# SCH_WINGLET_IO.net
KiCad netlist of a schematic drawn in Altium Designer
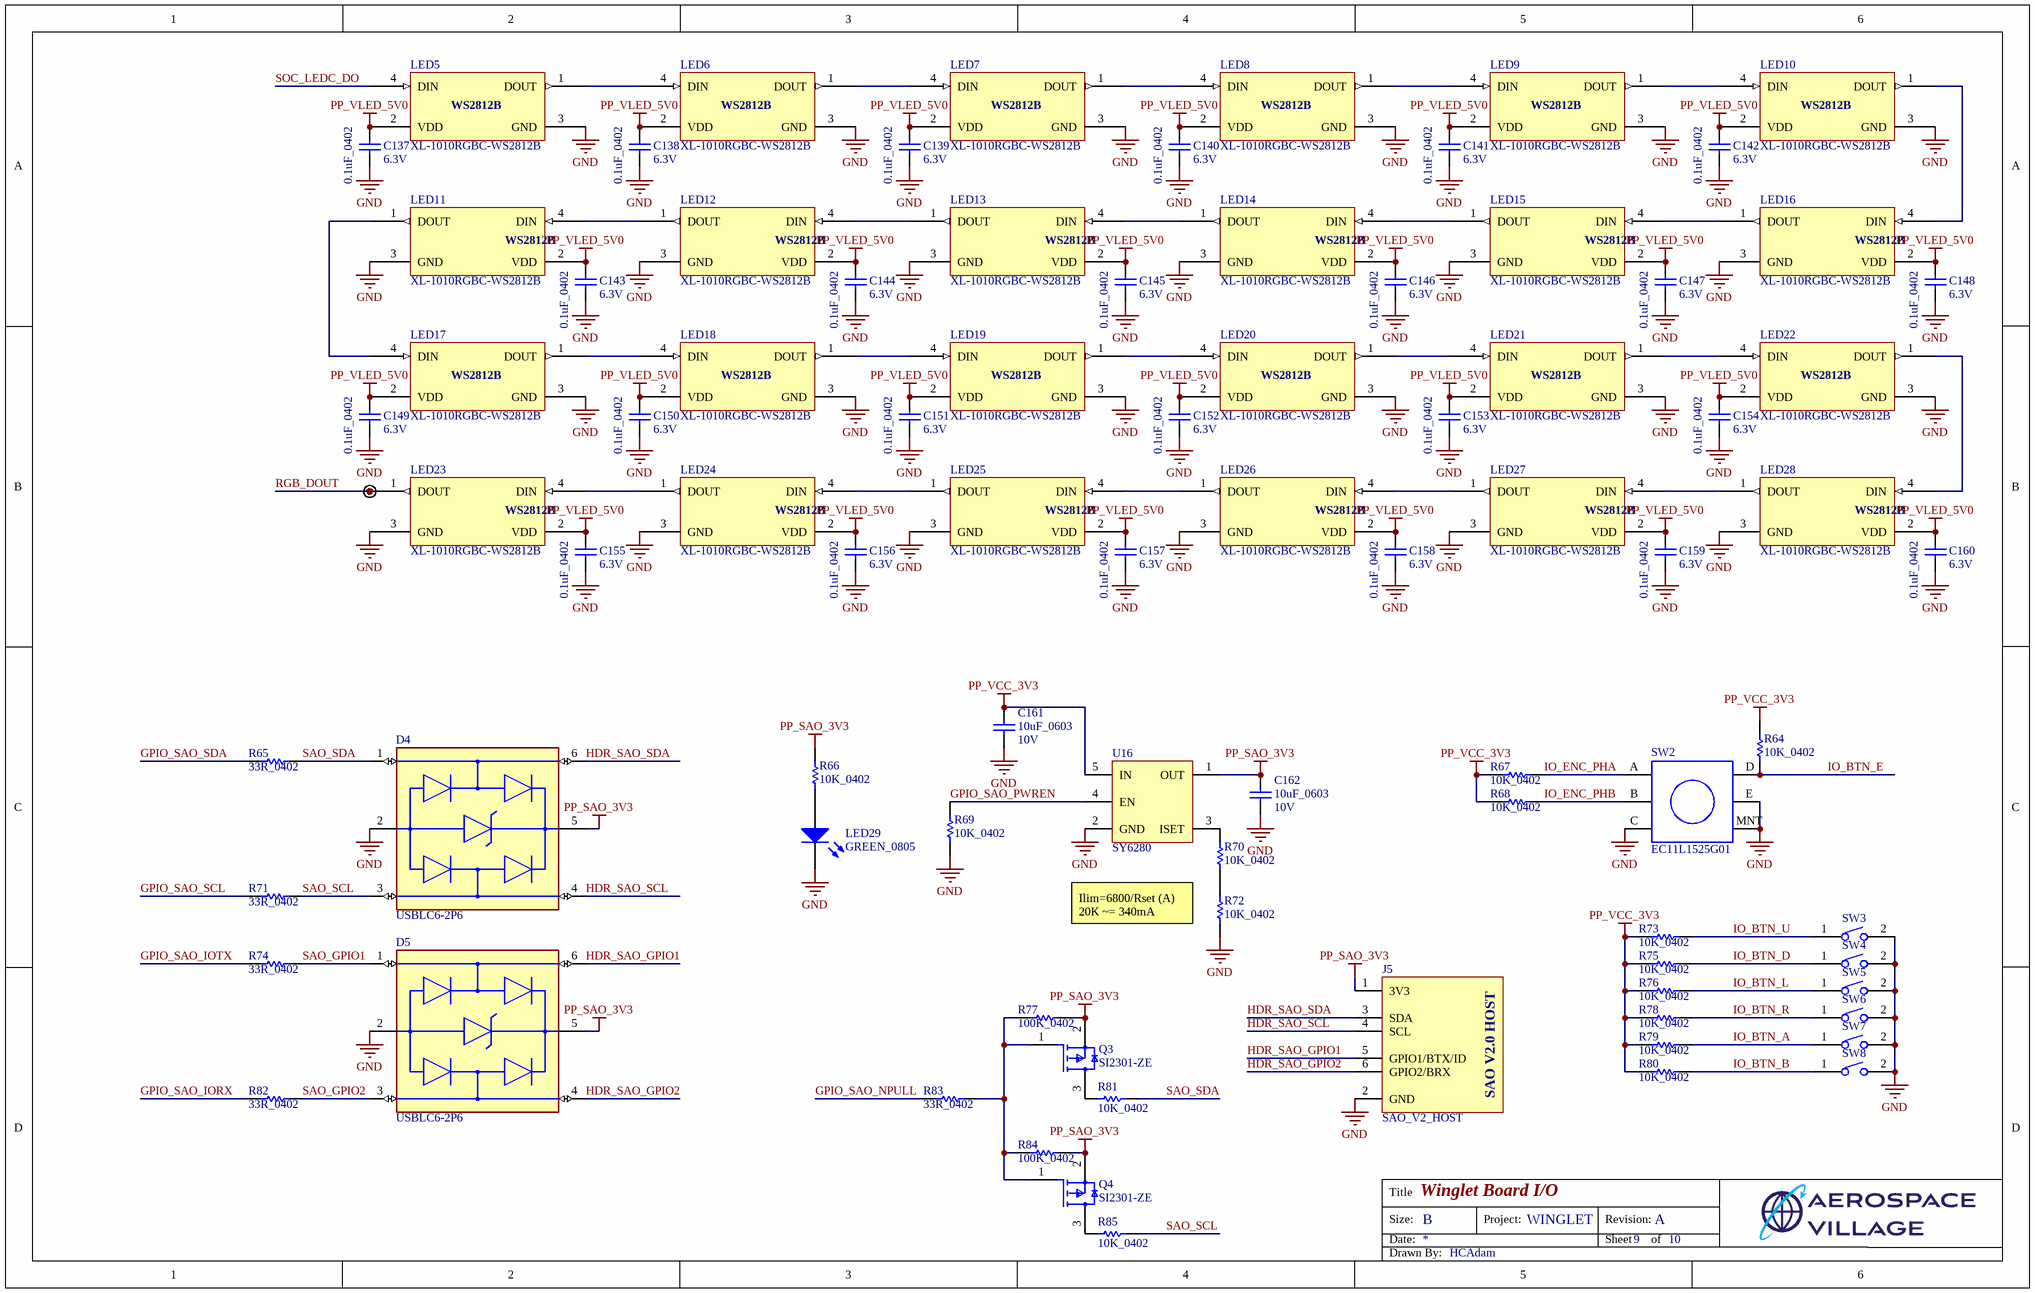
[diagram p0: SCH_WINGLET_IO.SchDoc]

(export (version "E")
  (design (tool "Eeschema 10.0.6"))
  (components
    (comp (ref "C137")
      (value "0.1uF_0402")
      (footprint "CAPC1005X56X25NL10T15")
      (description "04026D104KAT2A")
      (fields (field (name "MANUFACTURER") "AVX Interconnect / Elco") (field (name "VOLTAGE RATING") "6.3V"))
      (libsource (lib "Altium Content Vault") (part "CAP"))
    )
    (comp (ref "C138")
      (value "0.1uF_0402")
      (footprint "CAPC1005X56X25NL10T15")
      (description "04026D104KAT2A")
      (fields (field (name "MANUFACTURER") "AVX Interconnect / Elco") (field (name "VOLTAGE RATING") "6.3V"))
      (libsource (lib "Altium Content Vault") (part "CAP"))
    )
    (comp (ref "C139")
      (value "0.1uF_0402")
      (footprint "CAPC1005X56X25NL10T15")
      (description "04026D104KAT2A")
      (fields (field (name "MANUFACTURER") "AVX Interconnect / Elco") (field (name "VOLTAGE RATING") "6.3V"))
      (libsource (lib "Altium Content Vault") (part "CAP"))
    )
    (comp (ref "C140")
      (value "0.1uF_0402")
      (footprint "CAPC1005X56X25NL10T15")
      (description "04026D104KAT2A")
      (fields (field (name "MANUFACTURER") "AVX Interconnect / Elco") (field (name "VOLTAGE RATING") "6.3V"))
      (libsource (lib "Altium Content Vault") (part "CAP"))
    )
    (comp (ref "C141")
      (value "0.1uF_0402")
      (footprint "CAPC1005X56X25NL10T15")
      (description "04026D104KAT2A")
      (fields (field (name "MANUFACTURER") "AVX Interconnect / Elco") (field (name "VOLTAGE RATING") "6.3V"))
      (libsource (lib "Altium Content Vault") (part "CAP"))
    )
    (comp (ref "C142")
      (value "0.1uF_0402")
      (footprint "CAPC1005X56X25NL10T15")
      (description "04026D104KAT2A")
      (fields (field (name "MANUFACTURER") "AVX Interconnect / Elco") (field (name "VOLTAGE RATING") "6.3V"))
      (libsource (lib "Altium Content Vault") (part "CAP"))
    )
    (comp (ref "C143")
      (value "0.1uF_0402")
      (footprint "CAPC1005X56X25NL10T15")
      (description "04026D104KAT2A")
      (fields (field (name "MANUFACTURER") "AVX Interconnect / Elco") (field (name "VOLTAGE RATING") "6.3V"))
      (libsource (lib "Altium Content Vault") (part "CAP"))
    )
    (comp (ref "C144")
      (value "0.1uF_0402")
      (footprint "CAPC1005X56X25NL10T15")
      (description "04026D104KAT2A")
      (fields (field (name "MANUFACTURER") "AVX Interconnect / Elco") (field (name "VOLTAGE RATING") "6.3V"))
      (libsource (lib "Altium Content Vault") (part "CAP"))
    )
    (comp (ref "C145")
      (value "0.1uF_0402")
      (footprint "CAPC1005X56X25NL10T15")
      (description "04026D104KAT2A")
      (fields (field (name "MANUFACTURER") "AVX Interconnect / Elco") (field (name "VOLTAGE RATING") "6.3V"))
      (libsource (lib "Altium Content Vault") (part "CAP"))
    )
    (comp (ref "C146")
      (value "0.1uF_0402")
      (footprint "CAPC1005X56X25NL10T15")
      (description "04026D104KAT2A")
      (fields (field (name "MANUFACTURER") "AVX Interconnect / Elco") (field (name "VOLTAGE RATING") "6.3V"))
      (libsource (lib "Altium Content Vault") (part "CAP"))
    )
    (comp (ref "C147")
      (value "0.1uF_0402")
      (footprint "CAPC1005X56X25NL10T15")
      (description "04026D104KAT2A")
      (fields (field (name "MANUFACTURER") "AVX Interconnect / Elco") (field (name "VOLTAGE RATING") "6.3V"))
      (libsource (lib "Altium Content Vault") (part "CAP"))
    )
    (comp (ref "C148")
      (value "0.1uF_0402")
      (footprint "CAPC1005X56X25NL10T15")
      (description "04026D104KAT2A")
      (fields (field (name "MANUFACTURER") "AVX Interconnect / Elco") (field (name "VOLTAGE RATING") "6.3V"))
      (libsource (lib "Altium Content Vault") (part "CAP"))
    )
    (comp (ref "C149")
      (value "0.1uF_0402")
      (footprint "CAPC1005X56X25NL10T15")
      (description "04026D104KAT2A")
      (fields (field (name "MANUFACTURER") "AVX Interconnect / Elco") (field (name "VOLTAGE RATING") "6.3V"))
      (libsource (lib "Altium Content Vault") (part "CAP"))
    )
    (comp (ref "C150")
      (value "0.1uF_0402")
      (footprint "CAPC1005X56X25NL10T15")
      (description "04026D104KAT2A")
      (fields (field (name "MANUFACTURER") "AVX Interconnect / Elco") (field (name "VOLTAGE RATING") "6.3V"))
      (libsource (lib "Altium Content Vault") (part "CAP"))
    )
    (comp (ref "C151")
      (value "0.1uF_0402")
      (footprint "CAPC1005X56X25NL10T15")
      (description "04026D104KAT2A")
      (fields (field (name "MANUFACTURER") "AVX Interconnect / Elco") (field (name "VOLTAGE RATING") "6.3V"))
      (libsource (lib "Altium Content Vault") (part "CAP"))
    )
    (comp (ref "C152")
      (value "0.1uF_0402")
      (footprint "CAPC1005X56X25NL10T15")
      (description "04026D104KAT2A")
      (fields (field (name "MANUFACTURER") "AVX Interconnect / Elco") (field (name "VOLTAGE RATING") "6.3V"))
      (libsource (lib "Altium Content Vault") (part "CAP"))
    )
    (comp (ref "C153")
      (value "0.1uF_0402")
      (footprint "CAPC1005X56X25NL10T15")
      (description "04026D104KAT2A")
      (fields (field (name "MANUFACTURER") "AVX Interconnect / Elco") (field (name "VOLTAGE RATING") "6.3V"))
      (libsource (lib "Altium Content Vault") (part "CAP"))
    )
    (comp (ref "C154")
      (value "0.1uF_0402")
      (footprint "CAPC1005X56X25NL10T15")
      (description "04026D104KAT2A")
      (fields (field (name "MANUFACTURER") "AVX Interconnect / Elco") (field (name "VOLTAGE RATING") "6.3V"))
      (libsource (lib "Altium Content Vault") (part "CAP"))
    )
    (comp (ref "C155")
      (value "0.1uF_0402")
      (footprint "CAPC1005X56X25NL10T15")
      (description "04026D104KAT2A")
      (fields (field (name "MANUFACTURER") "AVX Interconnect / Elco") (field (name "VOLTAGE RATING") "6.3V"))
      (libsource (lib "Altium Content Vault") (part "CAP"))
    )
    (comp (ref "C156")
      (value "0.1uF_0402")
      (footprint "CAPC1005X56X25NL10T15")
      (description "04026D104KAT2A")
      (fields (field (name "MANUFACTURER") "AVX Interconnect / Elco") (field (name "VOLTAGE RATING") "6.3V"))
      (libsource (lib "Altium Content Vault") (part "CAP"))
    )
    (comp (ref "C157")
      (value "0.1uF_0402")
      (footprint "CAPC1005X56X25NL10T15")
      (description "04026D104KAT2A")
      (fields (field (name "MANUFACTURER") "AVX Interconnect / Elco") (field (name "VOLTAGE RATING") "6.3V"))
      (libsource (lib "Altium Content Vault") (part "CAP"))
    )
    (comp (ref "C158")
      (value "0.1uF_0402")
      (footprint "CAPC1005X56X25NL10T15")
      (description "04026D104KAT2A")
      (fields (field (name "MANUFACTURER") "AVX Interconnect / Elco") (field (name "VOLTAGE RATING") "6.3V"))
      (libsource (lib "Altium Content Vault") (part "CAP"))
    )
    (comp (ref "C159")
      (value "0.1uF_0402")
      (footprint "CAPC1005X56X25NL10T15")
      (description "04026D104KAT2A")
      (fields (field (name "MANUFACTURER") "AVX Interconnect / Elco") (field (name "VOLTAGE RATING") "6.3V"))
      (libsource (lib "Altium Content Vault") (part "CAP"))
    )
    (comp (ref "C160")
      (value "0.1uF_0402")
      (footprint "CAPC1005X56X25NL10T15")
      (description "04026D104KAT2A")
      (fields (field (name "MANUFACTURER") "AVX Interconnect / Elco") (field (name "VOLTAGE RATING") "6.3V"))
      (libsource (lib "Altium Content Vault") (part "CAP"))
    )
    (comp (ref "C161")
      (value "10uF_0603")
      (footprint "CAPC1609X100X15NL20")
      (fields
        (field (name "PART NUMBER") "TACL106M006XTA")
        (field (name "MANUFACTURER") "AVX Interconnect / Elco")
        (field (name "VOLTAGE RATING") "10V")
      )
      (libsource (lib "Altium Content Vault") (part "CAP"))
    )
    (comp (ref "C162")
      (value "10uF_0603")
      (footprint "CAPC1609X100X15NL20")
      (fields
        (field (name "PART NUMBER") "TACL106M006XTA")
        (field (name "MANUFACTURER") "AVX Interconnect / Elco")
        (field (name "VOLTAGE RATING") "10V")
      )
      (libsource (lib "Altium Content Vault") (part "CAP"))
    )
    (comp (ref "D4")
      (value "USBLC6-2P6")
      (footprint "FP-SOT-666-MFG")
      (description "TVS DIODE 5.25V 17V SOT666")
      (libsource (lib "Altium Content Vault") (part "c871e55f7e3243d341edbd671b98d92"))
    )
    (comp (ref "D5")
      (value "USBLC6-2P6")
      (footprint "FP-SOT-666-MFG")
      (description "TVS DIODE 5.25V 17V SOT666")
      (libsource (lib "Altium Content Vault") (part "c871e55f7e3243d341edbd671b98d92"))
    )
    (comp (ref "J5")
      (value "SAO_V2_HOST")
      (footprint "SAO_FEMALE")
      (description "SAO V2 Host (Female) Side")
      (libsource (lib "DCAV32_WINGLET_SCHLIB") (part "SAO_V2_HOST"))
    )
    (comp (ref "LED5")
      (value "XL-1010RGBC-WS2812B")
      (footprint "DFN3127P600-8N")
      (description "1010 RGB WS2812B LED 3.5-5.5V")
      (libsource (lib "DCAV32") (part "XL-1010RGBC-WS2812B"))
    )
    (comp (ref "LED6")
      (value "XL-1010RGBC-WS2812B")
      (footprint "DFN3127P600-8N")
      (description "1010 RGB WS2812B LED 3.5-5.5V")
      (libsource (lib "DCAV32") (part "XL-1010RGBC-WS2812B"))
    )
    (comp (ref "LED7")
      (value "XL-1010RGBC-WS2812B")
      (footprint "DFN3127P600-8N")
      (description "1010 RGB WS2812B LED 3.5-5.5V")
      (libsource (lib "DCAV32") (part "XL-1010RGBC-WS2812B"))
    )
    (comp (ref "LED8")
      (value "XL-1010RGBC-WS2812B")
      (footprint "DFN3127P600-8N")
      (description "1010 RGB WS2812B LED 3.5-5.5V")
      (libsource (lib "DCAV32") (part "XL-1010RGBC-WS2812B"))
    )
    (comp (ref "LED9")
      (value "XL-1010RGBC-WS2812B")
      (footprint "DFN3127P600-8N")
      (description "1010 RGB WS2812B LED 3.5-5.5V")
      (libsource (lib "DCAV32") (part "XL-1010RGBC-WS2812B"))
    )
    (comp (ref "LED10")
      (value "XL-1010RGBC-WS2812B")
      (footprint "DFN3127P600-8N")
      (description "1010 RGB WS2812B LED 3.5-5.5V")
      (libsource (lib "DCAV32") (part "XL-1010RGBC-WS2812B"))
    )
    (comp (ref "LED11")
      (value "XL-1010RGBC-WS2812B")
      (footprint "DFN3127P600-8N")
      (description "1010 RGB WS2812B LED 3.5-5.5V")
      (libsource (lib "") (part "XL-1010RGBC-WS2812B_1"))
    )
    (comp (ref "LED12")
      (value "XL-1010RGBC-WS2812B")
      (footprint "DFN3127P600-8N")
      (description "1010 RGB WS2812B LED 3.5-5.5V")
      (libsource (lib "") (part "XL-1010RGBC-WS2812B_1"))
    )
    (comp (ref "LED13")
      (value "XL-1010RGBC-WS2812B")
      (footprint "DFN3127P600-8N")
      (description "1010 RGB WS2812B LED 3.5-5.5V")
      (libsource (lib "") (part "XL-1010RGBC-WS2812B_1"))
    )
    (comp (ref "LED14")
      (value "XL-1010RGBC-WS2812B")
      (footprint "DFN3127P600-8N")
      (description "1010 RGB WS2812B LED 3.5-5.5V")
      (libsource (lib "") (part "XL-1010RGBC-WS2812B_1"))
    )
    (comp (ref "LED15")
      (value "XL-1010RGBC-WS2812B")
      (footprint "DFN3127P600-8N")
      (description "1010 RGB WS2812B LED 3.5-5.5V")
      (libsource (lib "") (part "XL-1010RGBC-WS2812B_1"))
    )
    (comp (ref "LED16")
      (value "XL-1010RGBC-WS2812B")
      (footprint "DFN3127P600-8N")
      (description "1010 RGB WS2812B LED 3.5-5.5V")
      (libsource (lib "") (part "XL-1010RGBC-WS2812B_1"))
    )
    (comp (ref "LED17")
      (value "XL-1010RGBC-WS2812B")
      (footprint "DFN3127P600-8N")
      (description "1010 RGB WS2812B LED 3.5-5.5V")
      (libsource (lib "DCAV32") (part "XL-1010RGBC-WS2812B"))
    )
    (comp (ref "LED18")
      (value "XL-1010RGBC-WS2812B")
      (footprint "DFN3127P600-8N")
      (description "1010 RGB WS2812B LED 3.5-5.5V")
      (libsource (lib "DCAV32") (part "XL-1010RGBC-WS2812B"))
    )
    (comp (ref "LED19")
      (value "XL-1010RGBC-WS2812B")
      (footprint "DFN3127P600-8N")
      (description "1010 RGB WS2812B LED 3.5-5.5V")
      (libsource (lib "DCAV32") (part "XL-1010RGBC-WS2812B"))
    )
    (comp (ref "LED20")
      (value "XL-1010RGBC-WS2812B")
      (footprint "DFN3127P600-8N")
      (description "1010 RGB WS2812B LED 3.5-5.5V")
      (libsource (lib "DCAV32") (part "XL-1010RGBC-WS2812B"))
    )
    (comp (ref "LED21")
      (value "XL-1010RGBC-WS2812B")
      (footprint "DFN3127P600-8N")
      (description "1010 RGB WS2812B LED 3.5-5.5V")
      (libsource (lib "DCAV32") (part "XL-1010RGBC-WS2812B"))
    )
    (comp (ref "LED22")
      (value "XL-1010RGBC-WS2812B")
      (footprint "DFN3127P600-8N")
      (description "1010 RGB WS2812B LED 3.5-5.5V")
      (libsource (lib "DCAV32") (part "XL-1010RGBC-WS2812B"))
    )
    (comp (ref "LED23")
      (value "XL-1010RGBC-WS2812B")
      (footprint "DFN3127P600-8N")
      (description "1010 RGB WS2812B LED 3.5-5.5V")
      (libsource (lib "") (part "XL-1010RGBC-WS2812B_1"))
    )
    (comp (ref "LED24")
      (value "XL-1010RGBC-WS2812B")
      (footprint "DFN3127P600-8N")
      (description "1010 RGB WS2812B LED 3.5-5.5V")
      (libsource (lib "") (part "XL-1010RGBC-WS2812B_1"))
    )
    (comp (ref "LED25")
      (value "XL-1010RGBC-WS2812B")
      (footprint "DFN3127P600-8N")
      (description "1010 RGB WS2812B LED 3.5-5.5V")
      (libsource (lib "") (part "XL-1010RGBC-WS2812B_1"))
    )
    (comp (ref "LED26")
      (value "XL-1010RGBC-WS2812B")
      (footprint "DFN3127P600-8N")
      (description "1010 RGB WS2812B LED 3.5-5.5V")
      (libsource (lib "") (part "XL-1010RGBC-WS2812B_1"))
    )
    (comp (ref "LED27")
      (value "XL-1010RGBC-WS2812B")
      (footprint "DFN3127P600-8N")
      (description "1010 RGB WS2812B LED 3.5-5.5V")
      (libsource (lib "") (part "XL-1010RGBC-WS2812B_1"))
    )
    (comp (ref "LED28")
      (value "XL-1010RGBC-WS2812B")
      (footprint "DFN3127P600-8N")
      (description "1010 RGB WS2812B LED 3.5-5.5V")
      (libsource (lib "") (part "XL-1010RGBC-WS2812B_1"))
    )
    (comp (ref "LED29")
      (value "GREEN_0805")
      (footprint "0805_A")
      (description "SMD mono-color Chip LED, WL-SMCW, Green\r\n150080GS75000")
      (fields (field (name "PARTNUMBER") "150080GS75000") (field (name "MANUFACTURER") "Wuerth Elektronik"))
      (libsource (lib "Altium Content Vault") (part "WE-LED_K1A2-2"))
    )
    (comp (ref "Q3")
      (value "SI2301-ZE")
      (footprint "FP-SOT23-MFG")
      (description "MOSFET P-CH 30V SOT23")
      (libsource (lib "Altium Content Vault") (part "d876440acba04c58a9f817a20952145"))
    )
    (comp (ref "Q4")
      (value "SI2301-ZE")
      (footprint "FP-SOT23-MFG")
      (description "MOSFET P-CH 30V SOT23")
      (libsource (lib "Altium Content Vault") (part "d876440acba04c58a9f817a20952145"))
    )
    (comp (ref "R64")
      (value "10K_0402")
      (footprint "RESC1005X40X25NL05T05")
      (fields (field (name "TOLERANCE") "1%") (field (name "MANUFACTURER") "Panasonic"))
      (libsource (lib "Altium Content Vault") (part "RES-2"))
    )
    (comp (ref "R65")
      (value "33R_0402")
      (footprint "RESC1005X40X25NL05T05")
      (description "ERJ2RKF33R0X")
      (fields (field (name "MANUFACTURER") "Panasonic"))
      (libsource (lib "Altium Content Vault") (part "RES"))
    )
    (comp (ref "R66")
      (value "10K_0402")
      (footprint "RESC1005X40X25NL05T05")
      (fields (field (name "TOLERANCE") "1%") (field (name "MANUFACTURER") "Panasonic"))
      (libsource (lib "Altium Content Vault") (part "RES-2"))
    )
    (comp (ref "R67")
      (value "10K_0402")
      (footprint "RESC1005X40X25NL05T05")
      (fields (field (name "TOLERANCE") "1%") (field (name "MANUFACTURER") "Panasonic"))
      (libsource (lib "Altium Content Vault") (part "RES-2"))
    )
    (comp (ref "R68")
      (value "10K_0402")
      (footprint "RESC1005X40X25NL05T05")
      (fields (field (name "TOLERANCE") "1%") (field (name "MANUFACTURER") "Panasonic"))
      (libsource (lib "Altium Content Vault") (part "RES-2"))
    )
    (comp (ref "R69")
      (value "10K_0402")
      (footprint "RESC1005X40X25NL05T05")
      (fields (field (name "TOLERANCE") "1%") (field (name "MANUFACTURER") "Panasonic"))
      (libsource (lib "Altium Content Vault") (part "RES-2"))
    )
    (comp (ref "R70")
      (value "10K_0402")
      (footprint "RESC1005X40X25NL05T05")
      (fields (field (name "TOLERANCE") "1%") (field (name "MANUFACTURER") "Panasonic"))
      (libsource (lib "Altium Content Vault") (part "RES-2"))
    )
    (comp (ref "R71")
      (value "33R_0402")
      (footprint "RESC1005X40X25NL05T05")
      (description "ERJ2RKF33R0X")
      (fields (field (name "MANUFACTURER") "Panasonic"))
      (libsource (lib "Altium Content Vault") (part "RES"))
    )
    (comp (ref "R72")
      (value "10K_0402")
      (footprint "RESC1005X40X25NL05T05")
      (fields (field (name "TOLERANCE") "1%") (field (name "MANUFACTURER") "Panasonic"))
      (libsource (lib "Altium Content Vault") (part "RES-2"))
    )
    (comp (ref "R73")
      (value "10K_0402")
      (footprint "RESC1005X40X25NL05T05")
      (fields (field (name "TOLERANCE") "1%") (field (name "MANUFACTURER") "Panasonic"))
      (libsource (lib "Altium Content Vault") (part "RES-2"))
    )
    (comp (ref "R74")
      (value "33R_0402")
      (footprint "RESC1005X40X25NL05T05")
      (description "ERJ2RKF33R0X")
      (fields (field (name "MANUFACTURER") "Panasonic"))
      (libsource (lib "Altium Content Vault") (part "RES"))
    )
    (comp (ref "R75")
      (value "10K_0402")
      (footprint "RESC1005X40X25NL05T05")
      (fields (field (name "TOLERANCE") "1%") (field (name "MANUFACTURER") "Panasonic"))
      (libsource (lib "Altium Content Vault") (part "RES-2"))
    )
    (comp (ref "R76")
      (value "10K_0402")
      (footprint "RESC1005X40X25NL05T05")
      (fields (field (name "TOLERANCE") "1%") (field (name "MANUFACTURER") "Panasonic"))
      (libsource (lib "Altium Content Vault") (part "RES-2"))
    )
    (comp (ref "R77")
      (value "100K_0402")
      (footprint "RESC1005X40X25NL05T10")
      (description "RC0402FR-07100KL")
      (fields (field (name "MANUFACTURER") "Yageo / Phycomp"))
      (libsource (lib "Altium Content Vault") (part "RES"))
    )
    (comp (ref "R78")
      (value "10K_0402")
      (footprint "RESC1005X40X25NL05T05")
      (fields (field (name "TOLERANCE") "1%") (field (name "MANUFACTURER") "Panasonic"))
      (libsource (lib "Altium Content Vault") (part "RES-2"))
    )
    (comp (ref "R79")
      (value "10K_0402")
      (footprint "RESC1005X40X25NL05T05")
      (fields (field (name "TOLERANCE") "1%") (field (name "MANUFACTURER") "Panasonic"))
      (libsource (lib "Altium Content Vault") (part "RES-2"))
    )
    (comp (ref "R80")
      (value "10K_0402")
      (footprint "RESC1005X40X25NL05T05")
      (fields (field (name "TOLERANCE") "1%") (field (name "MANUFACTURER") "Panasonic"))
      (libsource (lib "Altium Content Vault") (part "RES-2"))
    )
    (comp (ref "R81")
      (value "10K_0402")
      (footprint "RESC1005X40X25NL05T05")
      (fields (field (name "TOLERANCE") "1%") (field (name "MANUFACTURER") "Panasonic"))
      (libsource (lib "Altium Content Vault") (part "RES-2"))
    )
    (comp (ref "R82")
      (value "33R_0402")
      (footprint "RESC1005X40X25NL05T05")
      (description "ERJ2RKF33R0X")
      (fields (field (name "MANUFACTURER") "Panasonic"))
      (libsource (lib "Altium Content Vault") (part "RES"))
    )
    (comp (ref "R83")
      (value "33R_0402")
      (footprint "RESC1005X40X25NL05T05")
      (description "ERJ2RKF33R0X")
      (fields (field (name "MANUFACTURER") "Panasonic"))
      (libsource (lib "Altium Content Vault") (part "RES"))
    )
    (comp (ref "R84")
      (value "100K_0402")
      (footprint "RESC1005X40X25NL05T10")
      (description "RC0402FR-07100KL")
      (fields (field (name "MANUFACTURER") "Yageo / Phycomp"))
      (libsource (lib "Altium Content Vault") (part "RES"))
    )
    (comp (ref "R85")
      (value "10K_0402")
      (footprint "RESC1005X40X25NL05T05")
      (fields (field (name "TOLERANCE") "1%") (field (name "MANUFACTURER") "Panasonic"))
      (libsource (lib "Altium Content Vault") (part "RES-2"))
    )
    (comp (ref "SW2")
      (value "EC11L1525G01")
      (footprint "LCSC_ALPS_EC11L1525G01")
      (description "EC11L1525G01 Rotary Encoder with Pushbutton")
      (libsource (lib "DCAV32_WINGLET_SCHLIB") (part "EC11L1525G01"))
    )
    (comp (ref "SW3")
      (value "C5127964")
      (footprint "LCSC_SMD_SW_MED")
      (description "SMD SPST Tactile Switch\r\nC5127964")
      (libsource (lib "DCAV32_WINGLET_SCHLIB") (part "SMD_SW_MED"))
    )
    (comp (ref "SW4")
      (value "C5127964")
      (footprint "LCSC_SMD_SW_MED")
      (description "SMD SPST Tactile Switch\r\nC5127964")
      (libsource (lib "DCAV32_WINGLET_SCHLIB") (part "SMD_SW_MED"))
    )
    (comp (ref "SW5")
      (value "C5127964")
      (footprint "LCSC_SMD_SW_MED")
      (description "SMD SPST Tactile Switch\r\nC5127964")
      (libsource (lib "DCAV32_WINGLET_SCHLIB") (part "SMD_SW_MED"))
    )
    (comp (ref "SW6")
      (value "C5127964")
      (footprint "LCSC_SMD_SW_MED")
      (description "SMD SPST Tactile Switch\r\nC5127964")
      (libsource (lib "DCAV32_WINGLET_SCHLIB") (part "SMD_SW_MED"))
    )
    (comp (ref "SW7")
      (value "C5127964")
      (footprint "LCSC_SMD_SW_MED")
      (description "SMD SPST Tactile Switch\r\nC5127964")
      (libsource (lib "DCAV32_WINGLET_SCHLIB") (part "SMD_SW_MED"))
    )
    (comp (ref "SW8")
      (value "C5127964")
      (footprint "LCSC_SMD_SW_MED")
      (description "SMD SPST Tactile Switch\r\nC5127964")
      (libsource (lib "DCAV32_WINGLET_SCHLIB") (part "SMD_SW_MED"))
    )
    (comp (ref "TP28")
      (value "TESTPOINT")
      (footprint "TESTPOINT-0.7MM-SINGLE-LAYER")
      (description "TESTPOINT SINGLE LAYER 0.7MM")
      (libsource (lib "DCAV32_WINGLET_SCHLIB") (part "TP_07"))
    )
    (comp (ref "U16")
      (value "SY6280")
      (footprint "SOT95P292X115-5N")
      (description "Low Loss Power Distribution Switch")
      (libsource (lib "DCAV32") (part "SY6280"))
    )
  )
  (nets
    (net (code "1") (name "/GPIO_SAO_IORX") (class "Default")
      (node (ref "R82") (pin "1") (pinfunction "1_1") (pintype "passive"))
    )
    (net (code "2") (name "/GPIO_SAO_IOTX") (class "Default")
      (node (ref "R74") (pin "1") (pinfunction "1_1") (pintype "passive"))
    )
    (net (code "3") (name "/GPIO_SAO_NPULL") (class "Default")
      (node (ref "R83") (pin "1") (pinfunction "1_1") (pintype "passive"))
    )
    (net (code "4") (name "/GPIO_SAO_PWREN") (class "Default")
      (node (ref "R69") (pin "1") (pinfunction "1_1") (pintype "passive"))
      (node (ref "U16") (pin "4") (pinfunction "EN_4") (pintype "passive"))
    )
    (net (code "5") (name "/GPIO_SAO_SCL") (class "Default")
      (node (ref "R71") (pin "1") (pinfunction "1_1") (pintype "passive"))
    )
    (net (code "6") (name "/GPIO_SAO_SDA") (class "Default")
      (node (ref "R65") (pin "1") (pinfunction "1_1") (pintype "passive"))
    )
    (net (code "7") (name "/HDR_SAO_GPIO1") (class "Default")
      (node (ref "D5") (pin "6") (pinfunction "I/O1_6") (pintype "bidirectional"))
      (node (ref "J5") (pin "5") (pinfunction "GPIO1/BTX/ID_5") (pintype "passive"))
    )
    (net (code "8") (name "/HDR_SAO_GPIO2") (class "Default")
      (node (ref "D5") (pin "4") (pinfunction "I/O2_4") (pintype "bidirectional"))
      (node (ref "J5") (pin "6") (pinfunction "GPIO2/BRX_6") (pintype "passive"))
    )
    (net (code "9") (name "/HDR_SAO_SCL") (class "Default")
      (node (ref "D4") (pin "4") (pinfunction "I/O2_4") (pintype "bidirectional"))
      (node (ref "J5") (pin "4") (pinfunction "SCL_4") (pintype "passive"))
    )
    (net (code "10") (name "/HDR_SAO_SDA") (class "Default")
      (node (ref "D4") (pin "6") (pinfunction "I/O1_6") (pintype "bidirectional"))
      (node (ref "J5") (pin "3") (pinfunction "SDA_3") (pintype "passive"))
    )
    (net (code "11") (name "/IO_BTN_A") (class "Default")
      (node (ref "R79") (pin "1") (pinfunction "1_1") (pintype "passive"))
      (node (ref "SW7") (pin "1") (pintype "passive"))
    )
    (net (code "12") (name "/IO_BTN_B") (class "Default")
      (node (ref "R80") (pin "1") (pinfunction "1_1") (pintype "passive"))
      (node (ref "SW8") (pin "1") (pintype "passive"))
    )
    (net (code "13") (name "/IO_BTN_D") (class "Default")
      (node (ref "R75") (pin "1") (pinfunction "1_1") (pintype "passive"))
      (node (ref "SW4") (pin "1") (pintype "passive"))
    )
    (net (code "14") (name "/IO_BTN_E") (class "Default")
      (node (ref "R64") (pin "1") (pinfunction "1_1") (pintype "passive"))
      (node (ref "SW2") (pin "D") (pintype "passive"))
    )
    (net (code "15") (name "/IO_BTN_L") (class "Default")
      (node (ref "R76") (pin "1") (pinfunction "1_1") (pintype "passive"))
      (node (ref "SW5") (pin "1") (pintype "passive"))
    )
    (net (code "16") (name "/IO_BTN_R") (class "Default")
      (node (ref "R78") (pin "1") (pinfunction "1_1") (pintype "passive"))
      (node (ref "SW6") (pin "1") (pintype "passive"))
    )
    (net (code "17") (name "/IO_BTN_U") (class "Default")
      (node (ref "R73") (pin "1") (pinfunction "1_1") (pintype "passive"))
      (node (ref "SW3") (pin "1") (pintype "passive"))
    )
    (net (code "18") (name "/IO_ENC_PHA") (class "Default")
      (node (ref "R67") (pin "1") (pinfunction "1_1") (pintype "passive"))
      (node (ref "SW2") (pin "A") (pintype "passive"))
    )
    (net (code "19") (name "/IO_ENC_PHB") (class "Default")
      (node (ref "R68") (pin "2") (pinfunction "2_2") (pintype "passive"))
      (node (ref "SW2") (pin "B") (pintype "passive"))
    )
    (net (code "20") (name "/RGB_DOUT") (class "Default")
      (node (ref "LED23") (pin "1") (pinfunction "DOUT_1") (pintype "output"))
      (node (ref "TP28") (pin "1") (pinfunction "1_1") (pintype "passive"))
    )
    (net (code "21") (name "/SAO_GPIO1") (class "Default")
      (node (ref "D5") (pin "1") (pinfunction "I/O1_1") (pintype "bidirectional"))
      (node (ref "R74") (pin "2") (pinfunction "2_2") (pintype "passive"))
    )
    (net (code "22") (name "/SAO_GPIO2") (class "Default")
      (node (ref "D5") (pin "3") (pinfunction "I/O2_3") (pintype "bidirectional"))
      (node (ref "R82") (pin "2") (pinfunction "2_2") (pintype "passive"))
    )
    (net (code "23") (name "/SAO_SCL") (class "Default")
      (node (ref "D4") (pin "3") (pinfunction "I/O2_3") (pintype "bidirectional"))
      (node (ref "R71") (pin "2") (pinfunction "2_2") (pintype "passive"))
      (node (ref "R85") (pin "1") (pinfunction "1_1") (pintype "passive"))
    )
    (net (code "24") (name "/SAO_SDA") (class "Default")
      (node (ref "D4") (pin "1") (pinfunction "I/O1_1") (pintype "bidirectional"))
      (node (ref "R65") (pin "2") (pinfunction "2_2") (pintype "passive"))
      (node (ref "R81") (pin "1") (pinfunction "1_1") (pintype "passive"))
    )
    (net (code "25") (name "/SOC_LEDC_DO") (class "Default")
      (node (ref "LED5") (pin "4") (pinfunction "DIN_4") (pintype "input"))
    )
    (net (code "26") (name "GND") (class "Default")
      (node (ref "C137") (pin "1") (pinfunction "1_1") (pintype "passive"))
      (node (ref "C138") (pin "1") (pinfunction "1_1") (pintype "passive"))
      (node (ref "C139") (pin "1") (pinfunction "1_1") (pintype "passive"))
      (node (ref "C140") (pin "1") (pinfunction "1_1") (pintype "passive"))
      (node (ref "C141") (pin "1") (pinfunction "1_1") (pintype "passive"))
      (node (ref "C142") (pin "1") (pinfunction "1_1") (pintype "passive"))
      (node (ref "C143") (pin "1") (pinfunction "1_1") (pintype "passive"))
      (node (ref "C144") (pin "1") (pinfunction "1_1") (pintype "passive"))
      (node (ref "C145") (pin "1") (pinfunction "1_1") (pintype "passive"))
      (node (ref "C146") (pin "1") (pinfunction "1_1") (pintype "passive"))
      (node (ref "C147") (pin "1") (pinfunction "1_1") (pintype "passive"))
      (node (ref "C148") (pin "1") (pinfunction "1_1") (pintype "passive"))
      (node (ref "C149") (pin "1") (pinfunction "1_1") (pintype "passive"))
      (node (ref "C150") (pin "1") (pinfunction "1_1") (pintype "passive"))
      (node (ref "C151") (pin "1") (pinfunction "1_1") (pintype "passive"))
      (node (ref "C152") (pin "1") (pinfunction "1_1") (pintype "passive"))
      (node (ref "C153") (pin "1") (pinfunction "1_1") (pintype "passive"))
      (node (ref "C154") (pin "1") (pinfunction "1_1") (pintype "passive"))
      (node (ref "C155") (pin "1") (pinfunction "1_1") (pintype "passive"))
      (node (ref "C156") (pin "1") (pinfunction "1_1") (pintype "passive"))
      (node (ref "C157") (pin "1") (pinfunction "1_1") (pintype "passive"))
      (node (ref "C158") (pin "1") (pinfunction "1_1") (pintype "passive"))
      (node (ref "C159") (pin "1") (pinfunction "1_1") (pintype "passive"))
      (node (ref "C160") (pin "1") (pinfunction "1_1") (pintype "passive"))
      (node (ref "C161") (pin "1") (pinfunction "1_1") (pintype "passive"))
      (node (ref "C162") (pin "1") (pinfunction "1_1") (pintype "passive"))
      (node (ref "D4") (pin "2") (pinfunction "GND_2") (pintype "power_in"))
      (node (ref "D5") (pin "2") (pinfunction "GND_2") (pintype "power_in"))
      (node (ref "J5") (pin "2") (pinfunction "GND_2") (pintype "passive"))
      (node (ref "LED10") (pin "3") (pinfunction "GND_3") (pintype "power_in"))
      (node (ref "LED11") (pin "3") (pinfunction "GND_3") (pintype "power_in"))
      (node (ref "LED12") (pin "3") (pinfunction "GND_3") (pintype "power_in"))
      (node (ref "LED13") (pin "3") (pinfunction "GND_3") (pintype "power_in"))
      (node (ref "LED14") (pin "3") (pinfunction "GND_3") (pintype "power_in"))
      (node (ref "LED15") (pin "3") (pinfunction "GND_3") (pintype "power_in"))
      (node (ref "LED16") (pin "3") (pinfunction "GND_3") (pintype "power_in"))
      (node (ref "LED17") (pin "3") (pinfunction "GND_3") (pintype "power_in"))
      (node (ref "LED18") (pin "3") (pinfunction "GND_3") (pintype "power_in"))
      (node (ref "LED19") (pin "3") (pinfunction "GND_3") (pintype "power_in"))
      (node (ref "LED20") (pin "3") (pinfunction "GND_3") (pintype "power_in"))
      (node (ref "LED21") (pin "3") (pinfunction "GND_3") (pintype "power_in"))
      (node (ref "LED22") (pin "3") (pinfunction "GND_3") (pintype "power_in"))
      (node (ref "LED23") (pin "3") (pinfunction "GND_3") (pintype "power_in"))
      (node (ref "LED24") (pin "3") (pinfunction "GND_3") (pintype "power_in"))
      (node (ref "LED25") (pin "3") (pinfunction "GND_3") (pintype "power_in"))
      (node (ref "LED26") (pin "3") (pinfunction "GND_3") (pintype "power_in"))
      (node (ref "LED27") (pin "3") (pinfunction "GND_3") (pintype "power_in"))
      (node (ref "LED28") (pin "3") (pinfunction "GND_3") (pintype "power_in"))
      (node (ref "LED29") (pin "1") (pinfunction "K_1") (pintype "passive"))
      (node (ref "LED5") (pin "3") (pinfunction "GND_3") (pintype "power_in"))
      (node (ref "LED6") (pin "3") (pinfunction "GND_3") (pintype "power_in"))
      (node (ref "LED7") (pin "3") (pinfunction "GND_3") (pintype "power_in"))
      (node (ref "LED8") (pin "3") (pinfunction "GND_3") (pintype "power_in"))
      (node (ref "LED9") (pin "3") (pinfunction "GND_3") (pintype "power_in"))
      (node (ref "R69") (pin "2") (pinfunction "2_2") (pintype "passive"))
      (node (ref "R72") (pin "2") (pinfunction "2_2") (pintype "passive"))
      (node (ref "SW2") (pin "C") (pintype "passive"))
      (node (ref "SW2") (pin "E") (pintype "passive"))
      (node (ref "SW2") (pin "MNT") (pintype "passive"))
      (node (ref "SW3") (pin "2") (pintype "passive"))
      (node (ref "SW4") (pin "2") (pintype "passive"))
      (node (ref "SW5") (pin "2") (pintype "passive"))
      (node (ref "SW6") (pin "2") (pintype "passive"))
      (node (ref "SW7") (pin "2") (pintype "passive"))
      (node (ref "SW8") (pin "2") (pintype "passive"))
      (node (ref "U16") (pin "2") (pinfunction "GND_2") (pintype "passive"))
    )
    (net (code "27") (name "Net-(LED5-DOUT)") (class "Default")
      (node (ref "LED5") (pin "1") (pinfunction "DOUT_1") (pintype "output"))
      (node (ref "LED6") (pin "4") (pinfunction "DIN_4") (pintype "input"))
    )
    (net (code "28") (name "Net-(LED6-DOUT)") (class "Default")
      (node (ref "LED6") (pin "1") (pinfunction "DOUT_1") (pintype "output"))
      (node (ref "LED7") (pin "4") (pinfunction "DIN_4") (pintype "input"))
    )
    (net (code "29") (name "Net-(LED7-DOUT)") (class "Default")
      (node (ref "LED7") (pin "1") (pinfunction "DOUT_1") (pintype "output"))
      (node (ref "LED8") (pin "4") (pinfunction "DIN_4") (pintype "input"))
    )
    (net (code "30") (name "Net-(LED8-DOUT)") (class "Default")
      (node (ref "LED8") (pin "1") (pinfunction "DOUT_1") (pintype "output"))
      (node (ref "LED9") (pin "4") (pinfunction "DIN_4") (pintype "input"))
    )
    (net (code "31") (name "Net-(LED10-DIN)") (class "Default")
      (node (ref "LED10") (pin "4") (pinfunction "DIN_4") (pintype "input"))
      (node (ref "LED9") (pin "1") (pinfunction "DOUT_1") (pintype "output"))
    )
    (net (code "32") (name "Net-(LED10-DOUT)") (class "Default")
      (node (ref "LED10") (pin "1") (pinfunction "DOUT_1") (pintype "output"))
      (node (ref "LED16") (pin "4") (pinfunction "DIN_4") (pintype "input"))
    )
    (net (code "33") (name "Net-(LED11-DIN)") (class "Default")
      (node (ref "LED11") (pin "4") (pinfunction "DIN_4") (pintype "input"))
      (node (ref "LED12") (pin "1") (pinfunction "DOUT_1") (pintype "output"))
    )
    (net (code "34") (name "Net-(LED11-DOUT)") (class "Default")
      (node (ref "LED11") (pin "1") (pinfunction "DOUT_1") (pintype "output"))
      (node (ref "LED17") (pin "4") (pinfunction "DIN_4") (pintype "input"))
    )
    (net (code "35") (name "Net-(LED12-DIN)") (class "Default")
      (node (ref "LED12") (pin "4") (pinfunction "DIN_4") (pintype "input"))
      (node (ref "LED13") (pin "1") (pinfunction "DOUT_1") (pintype "output"))
    )
    (net (code "36") (name "Net-(LED13-DIN)") (class "Default")
      (node (ref "LED13") (pin "4") (pinfunction "DIN_4") (pintype "input"))
      (node (ref "LED14") (pin "1") (pinfunction "DOUT_1") (pintype "output"))
    )
    (net (code "37") (name "Net-(LED14-DIN)") (class "Default")
      (node (ref "LED14") (pin "4") (pinfunction "DIN_4") (pintype "input"))
      (node (ref "LED15") (pin "1") (pinfunction "DOUT_1") (pintype "output"))
    )
    (net (code "38") (name "Net-(LED15-DIN)") (class "Default")
      (node (ref "LED15") (pin "4") (pinfunction "DIN_4") (pintype "input"))
      (node (ref "LED16") (pin "1") (pinfunction "DOUT_1") (pintype "output"))
    )
    (net (code "39") (name "Net-(LED17-DOUT)") (class "Default")
      (node (ref "LED17") (pin "1") (pinfunction "DOUT_1") (pintype "output"))
      (node (ref "LED18") (pin "4") (pinfunction "DIN_4") (pintype "input"))
    )
    (net (code "40") (name "Net-(LED18-DOUT)") (class "Default")
      (node (ref "LED18") (pin "1") (pinfunction "DOUT_1") (pintype "output"))
      (node (ref "LED19") (pin "4") (pinfunction "DIN_4") (pintype "input"))
    )
    (net (code "41") (name "Net-(LED19-DOUT)") (class "Default")
      (node (ref "LED19") (pin "1") (pinfunction "DOUT_1") (pintype "output"))
      (node (ref "LED20") (pin "4") (pinfunction "DIN_4") (pintype "input"))
    )
    (net (code "42") (name "Net-(LED20-DOUT)") (class "Default")
      (node (ref "LED20") (pin "1") (pinfunction "DOUT_1") (pintype "output"))
      (node (ref "LED21") (pin "4") (pinfunction "DIN_4") (pintype "input"))
    )
    (net (code "43") (name "Net-(LED21-DOUT)") (class "Default")
      (node (ref "LED21") (pin "1") (pinfunction "DOUT_1") (pintype "output"))
      (node (ref "LED22") (pin "4") (pinfunction "DIN_4") (pintype "input"))
    )
    (net (code "44") (name "Net-(LED22-DOUT)") (class "Default")
      (node (ref "LED22") (pin "1") (pinfunction "DOUT_1") (pintype "output"))
      (node (ref "LED28") (pin "4") (pinfunction "DIN_4") (pintype "input"))
    )
    (net (code "45") (name "Net-(LED23-DIN)") (class "Default")
      (node (ref "LED23") (pin "4") (pinfunction "DIN_4") (pintype "input"))
      (node (ref "LED24") (pin "1") (pinfunction "DOUT_1") (pintype "output"))
    )
    (net (code "46") (name "Net-(LED24-DIN)") (class "Default")
      (node (ref "LED24") (pin "4") (pinfunction "DIN_4") (pintype "input"))
      (node (ref "LED25") (pin "1") (pinfunction "DOUT_1") (pintype "output"))
    )
    (net (code "47") (name "Net-(LED25-DIN)") (class "Default")
      (node (ref "LED25") (pin "4") (pinfunction "DIN_4") (pintype "input"))
      (node (ref "LED26") (pin "1") (pinfunction "DOUT_1") (pintype "output"))
    )
    (net (code "48") (name "Net-(LED26-DIN)") (class "Default")
      (node (ref "LED26") (pin "4") (pinfunction "DIN_4") (pintype "input"))
      (node (ref "LED27") (pin "1") (pinfunction "DOUT_1") (pintype "output"))
    )
    (net (code "49") (name "Net-(LED27-DIN)") (class "Default")
      (node (ref "LED27") (pin "4") (pinfunction "DIN_4") (pintype "input"))
      (node (ref "LED28") (pin "1") (pinfunction "DOUT_1") (pintype "output"))
    )
    (net (code "50") (name "Net-(LED29-A)") (class "Default")
      (node (ref "LED29") (pin "2") (pinfunction "A_2") (pintype "passive"))
      (node (ref "R66") (pin "1") (pinfunction "1_1") (pintype "passive"))
    )
    (net (code "51") (name "Net-(Q3-D)") (class "Default")
      (node (ref "Q3") (pin "3") (pinfunction "D_3") (pintype "passive"))
      (node (ref "R81") (pin "2") (pinfunction "2_2") (pintype "passive"))
    )
    (net (code "52") (name "Net-(Q3-G)") (class "Default")
      (node (ref "Q3") (pin "1") (pinfunction "G_1") (pintype "passive"))
      (node (ref "Q4") (pin "1") (pinfunction "G_1") (pintype "passive"))
      (node (ref "R77") (pin "1") (pinfunction "1_1") (pintype "passive"))
      (node (ref "R83") (pin "2") (pinfunction "2_2") (pintype "passive"))
      (node (ref "R84") (pin "1") (pinfunction "1_1") (pintype "passive"))
    )
    (net (code "53") (name "Net-(Q4-D)") (class "Default")
      (node (ref "Q4") (pin "3") (pinfunction "D_3") (pintype "passive"))
      (node (ref "R85") (pin "2") (pinfunction "2_2") (pintype "passive"))
    )
    (net (code "54") (name "Net-(R70-Pad2)") (class "Default")
      (node (ref "R70") (pin "2") (pinfunction "2_2") (pintype "passive"))
      (node (ref "R72") (pin "1") (pinfunction "1_1") (pintype "passive"))
    )
    (net (code "55") (name "Net-(U16-ISET)") (class "Default")
      (node (ref "R70") (pin "1") (pinfunction "1_1") (pintype "passive"))
      (node (ref "U16") (pin "3") (pinfunction "ISET_3") (pintype "passive"))
    )
    (net (code "56") (name "PP_SAO_3V3") (class "Default")
      (node (ref "C162") (pin "2") (pinfunction "2_2") (pintype "passive"))
      (node (ref "D4") (pin "5") (pinfunction "VBUS_5") (pintype "power_in"))
      (node (ref "D5") (pin "5") (pinfunction "VBUS_5") (pintype "power_in"))
      (node (ref "J5") (pin "1") (pinfunction "3V3_1") (pintype "passive"))
      (node (ref "Q3") (pin "2") (pinfunction "S_2") (pintype "passive"))
      (node (ref "Q4") (pin "2") (pinfunction "S_2") (pintype "passive"))
      (node (ref "R66") (pin "2") (pinfunction "2_2") (pintype "passive"))
      (node (ref "R77") (pin "2") (pinfunction "2_2") (pintype "passive"))
      (node (ref "R84") (pin "2") (pinfunction "2_2") (pintype "passive"))
      (node (ref "U16") (pin "1") (pinfunction "OUT_1") (pintype "passive"))
    )
    (net (code "57") (name "PP_VCC_3V3") (class "Default")
      (node (ref "C161") (pin "2") (pinfunction "2_2") (pintype "passive"))
      (node (ref "R64") (pin "2") (pinfunction "2_2") (pintype "passive"))
      (node (ref "R67") (pin "2") (pinfunction "2_2") (pintype "passive"))
      (node (ref "R68") (pin "1") (pinfunction "1_1") (pintype "passive"))
      (node (ref "R73") (pin "2") (pinfunction "2_2") (pintype "passive"))
      (node (ref "R75") (pin "2") (pinfunction "2_2") (pintype "passive"))
      (node (ref "R76") (pin "2") (pinfunction "2_2") (pintype "passive"))
      (node (ref "R78") (pin "2") (pinfunction "2_2") (pintype "passive"))
      (node (ref "R79") (pin "2") (pinfunction "2_2") (pintype "passive"))
      (node (ref "R80") (pin "2") (pinfunction "2_2") (pintype "passive"))
      (node (ref "U16") (pin "5") (pinfunction "IN_5") (pintype "passive"))
    )
    (net (code "58") (name "PP_VLED_5V0") (class "Default")
      (node (ref "C137") (pin "2") (pinfunction "2_2") (pintype "passive"))
      (node (ref "C138") (pin "2") (pinfunction "2_2") (pintype "passive"))
      (node (ref "C139") (pin "2") (pinfunction "2_2") (pintype "passive"))
      (node (ref "C140") (pin "2") (pinfunction "2_2") (pintype "passive"))
      (node (ref "C141") (pin "2") (pinfunction "2_2") (pintype "passive"))
      (node (ref "C142") (pin "2") (pinfunction "2_2") (pintype "passive"))
      (node (ref "C143") (pin "2") (pinfunction "2_2") (pintype "passive"))
      (node (ref "C144") (pin "2") (pinfunction "2_2") (pintype "passive"))
      (node (ref "C145") (pin "2") (pinfunction "2_2") (pintype "passive"))
      (node (ref "C146") (pin "2") (pinfunction "2_2") (pintype "passive"))
      (node (ref "C147") (pin "2") (pinfunction "2_2") (pintype "passive"))
      (node (ref "C148") (pin "2") (pinfunction "2_2") (pintype "passive"))
      (node (ref "C149") (pin "2") (pinfunction "2_2") (pintype "passive"))
      (node (ref "C150") (pin "2") (pinfunction "2_2") (pintype "passive"))
      (node (ref "C151") (pin "2") (pinfunction "2_2") (pintype "passive"))
      (node (ref "C152") (pin "2") (pinfunction "2_2") (pintype "passive"))
      (node (ref "C153") (pin "2") (pinfunction "2_2") (pintype "passive"))
      (node (ref "C154") (pin "2") (pinfunction "2_2") (pintype "passive"))
      (node (ref "C155") (pin "2") (pinfunction "2_2") (pintype "passive"))
      (node (ref "C156") (pin "2") (pinfunction "2_2") (pintype "passive"))
      (node (ref "C157") (pin "2") (pinfunction "2_2") (pintype "passive"))
      (node (ref "C158") (pin "2") (pinfunction "2_2") (pintype "passive"))
      (node (ref "C159") (pin "2") (pinfunction "2_2") (pintype "passive"))
      (node (ref "C160") (pin "2") (pinfunction "2_2") (pintype "passive"))
      (node (ref "LED10") (pin "2") (pinfunction "VDD_2") (pintype "power_in"))
      (node (ref "LED11") (pin "2") (pinfunction "VDD_2") (pintype "power_in"))
      (node (ref "LED12") (pin "2") (pinfunction "VDD_2") (pintype "power_in"))
      (node (ref "LED13") (pin "2") (pinfunction "VDD_2") (pintype "power_in"))
      (node (ref "LED14") (pin "2") (pinfunction "VDD_2") (pintype "power_in"))
      (node (ref "LED15") (pin "2") (pinfunction "VDD_2") (pintype "power_in"))
      (node (ref "LED16") (pin "2") (pinfunction "VDD_2") (pintype "power_in"))
      (node (ref "LED17") (pin "2") (pinfunction "VDD_2") (pintype "power_in"))
      (node (ref "LED18") (pin "2") (pinfunction "VDD_2") (pintype "power_in"))
      (node (ref "LED19") (pin "2") (pinfunction "VDD_2") (pintype "power_in"))
      (node (ref "LED20") (pin "2") (pinfunction "VDD_2") (pintype "power_in"))
      (node (ref "LED21") (pin "2") (pinfunction "VDD_2") (pintype "power_in"))
      (node (ref "LED22") (pin "2") (pinfunction "VDD_2") (pintype "power_in"))
      (node (ref "LED23") (pin "2") (pinfunction "VDD_2") (pintype "power_in"))
      (node (ref "LED24") (pin "2") (pinfunction "VDD_2") (pintype "power_in"))
      (node (ref "LED25") (pin "2") (pinfunction "VDD_2") (pintype "power_in"))
      (node (ref "LED26") (pin "2") (pinfunction "VDD_2") (pintype "power_in"))
      (node (ref "LED27") (pin "2") (pinfunction "VDD_2") (pintype "power_in"))
      (node (ref "LED28") (pin "2") (pinfunction "VDD_2") (pintype "power_in"))
      (node (ref "LED5") (pin "2") (pinfunction "VDD_2") (pintype "power_in"))
      (node (ref "LED6") (pin "2") (pinfunction "VDD_2") (pintype "power_in"))
      (node (ref "LED7") (pin "2") (pinfunction "VDD_2") (pintype "power_in"))
      (node (ref "LED8") (pin "2") (pinfunction "VDD_2") (pintype "power_in"))
      (node (ref "LED9") (pin "2") (pinfunction "VDD_2") (pintype "power_in"))
    )
  )
)
